# AEMBLINK-R2.net
KiCad netlist of a schematic drawn in EAGLE
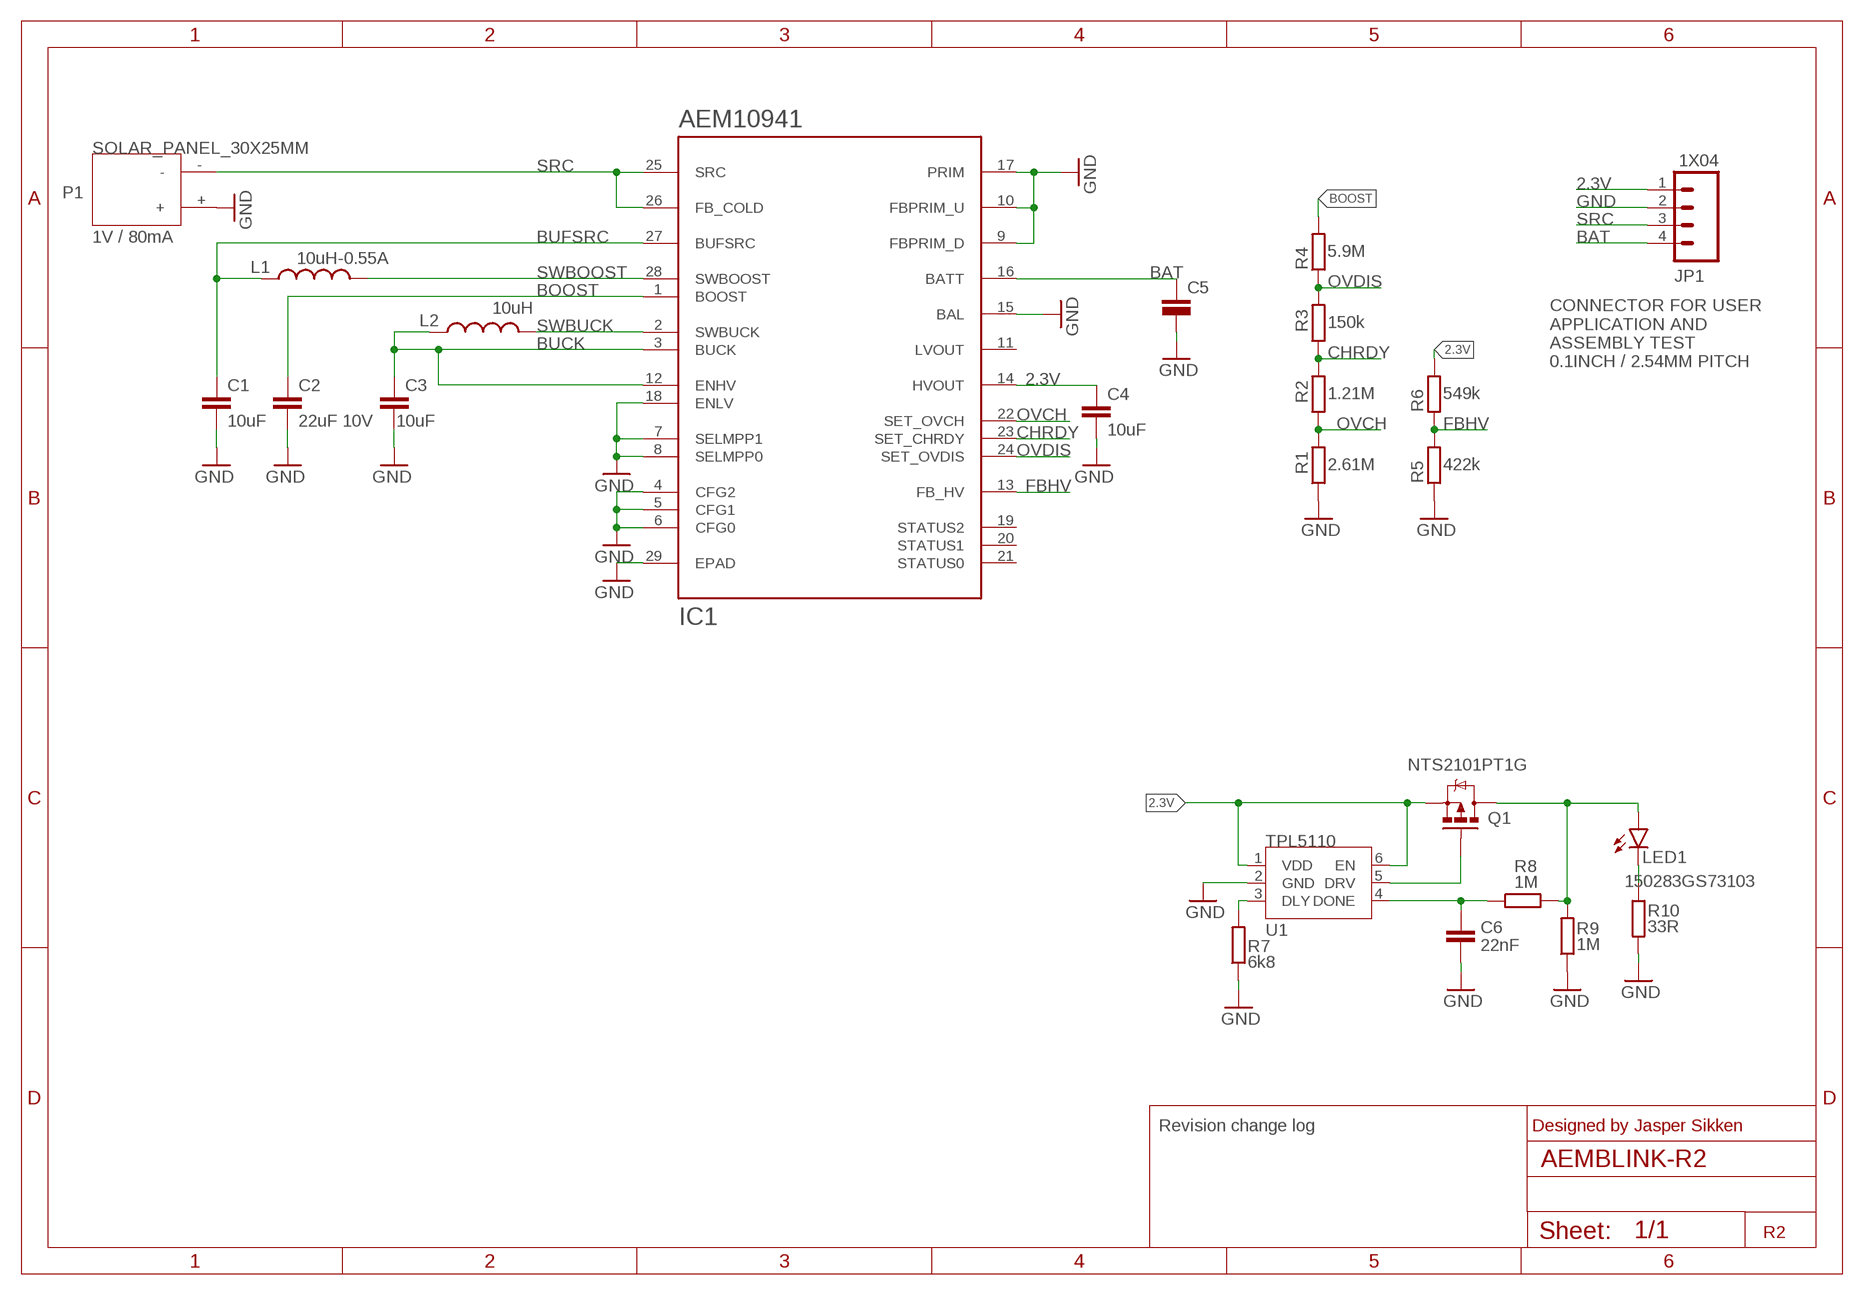
[diagram p0: schematic, sheet 1]

(export (version "E")
  (design (tool "Eeschema 10.0.6"))
  (components
    (comp (ref "C1")
      (value "10uF")
      (footprint "eagle-import:C0603")
      (fields
        (field (name "MF") "Taiyo Yuden")
        (field (name "MPN") "LMK107BBJ106MALT")
        (field (name "MF_1") "KEYSTONE")
        (field (name "MPN_1") "1049P")
      )
      (libsource (lib "eagle-import") (part "C0603_10UF"))
    )
    (comp (ref "C2")
      (value "22uF 10V")
      (footprint "eagle-import:C0603")
      (fields
        (field (name "MF") "Murata")
        (field (name "MPN") "GRM188R61A226ME15D")
        (field (name "MF_1") "TDK")
        (field (name "MPN_1") "CGA5L1X7S1A226M160AC")
      )
      (libsource (lib "eagle-import") (part "C0603_22UF"))
    )
    (comp (ref "C3")
      (value "10uF")
      (footprint "eagle-import:C0603")
      (fields
        (field (name "MF") "Taiyo Yuden")
        (field (name "MPN") "LMK107BBJ106MALT")
        (field (name "MF_1") "KEYSTONE")
        (field (name "MPN_1") "1049P")
      )
      (libsource (lib "eagle-import") (part "C0603_10UF"))
    )
    (comp (ref "C4")
      (value "10uF")
      (footprint "eagle-import:C0603")
      (fields
        (field (name "MF") "Taiyo Yuden")
        (field (name "MPN") "LMK107BBJ106MALT")
        (field (name "MF_1") "KEYSTONE")
        (field (name "MPN_1") "1049P")
      )
      (libsource (lib "eagle-import") (part "C0603_10UF"))
    )
    (comp (ref "C5")
      (value "SUPERCAPVEL08203R8306G")
      (footprint "eagle-import:C_RADIAL_20L8D5P0.8H_HOR")
      (libsource (lib "eagle-import") (part "SUPERCAPVEL08203R8306G"))
    )
    (comp (ref "C6")
      (value "22nF")
      (footprint "eagle-import:C0603")
      (libsource (lib "eagle-import") (part "C0603_10NF"))
    )
    (comp (ref "IC1")
      (value "AEM10941")
      (footprint "eagle-import:QFN50P505X505X90-28")
      (fields (field (name "MF") "e-peas"))
      (libsource (lib "eagle-import") (part "AEM10941"))
    )
    (comp (ref "JP1")
      (value "1X04")
      (footprint "eagle-import:1X04_2.54MM_ROUND_NOSILK")
      (libsource (lib "eagle-import") (part "1X04"))
    )
    (comp (ref "L1")
      (value "10uH-0.55A")
      (footprint "eagle-import:LPS4012")
      (fields
        (field (name "MF") "Coilcraft")
        (field (name "MPN") "LPS4012-103MRB")
        (field (name "MF_1") "BOURNS")
        (field (name "MPN_1") "SRN2009T-100M")
      )
      (libsource (lib "eagle-import") (part "L3.9X3.9_10UH_0.55A"))
    )
    (comp (ref "L2")
      (value "10uH")
      (footprint "eagle-import:L0603")
      (fields
        (field (name "MF") "TDK")
        (field (name "MPN") "MLZ1608M100WT")
        (field (name "MF_1") "TAIYO YUDEN")
        (field (name "MPN_1") "CK2125100M-T")
      )
      (libsource (lib "eagle-import") (part "L0603_10UH"))
    )
    (comp (ref "LED1")
      (value "150283GS73103")
      (footprint "eagle-import:150283GS73103")
      (libsource (lib "eagle-import") (part "150283GS73103"))
    )
    (comp (ref "P1")
      (value "SOLAR_PANEL_30X25MM")
      (footprint "eagle-import:SOLAR_PANEL_30X25")
      (libsource (lib "eagle-import") (part "SOLAR_PANEL_30X25MM"))
    )
    (comp (ref "Q1")
      (value "NTS2101PT1G")
      (footprint "eagle-import:SOT323")
      (libsource (lib "eagle-import") (part "MOSFET-P-CHANNEL-DMP2160UW"))
    )
    (comp (ref "R1")
      (value "2.61M")
      (footprint "eagle-import:R0402")
      (fields (field (name "MF") "Walsin") (field (name "MPN") "WR04X1004FTL"))
      (libsource (lib "eagle-import") (part "R0402_1M"))
    )
    (comp (ref "R2")
      (value "1.21M")
      (footprint "eagle-import:R0402")
      (fields (field (name "MF") "Walsin") (field (name "MPN") "WR04X1004FTL"))
      (libsource (lib "eagle-import") (part "R0402_1M"))
    )
    (comp (ref "R3")
      (value "150k")
      (footprint "eagle-import:R0402")
      (fields (field (name "MF") "Walsin") (field (name "MPN") "WR04X1004FTL"))
      (libsource (lib "eagle-import") (part "R0402_1M"))
    )
    (comp (ref "R4")
      (value "5.9M")
      (footprint "eagle-import:R0402")
      (fields (field (name "MF") "Walsin") (field (name "MPN") "WR04X1004FTL"))
      (libsource (lib "eagle-import") (part "R0402_1M"))
    )
    (comp (ref "R5")
      (value "422k")
      (footprint "eagle-import:R0402")
      (fields (field (name "MF") "Walsin") (field (name "MPN") "WR04X1004FTL"))
      (libsource (lib "eagle-import") (part "R0402_1M"))
    )
    (comp (ref "R6")
      (value "549k")
      (footprint "eagle-import:R0402")
      (fields (field (name "MF") "Walsin") (field (name "MPN") "WR04X1004FTL"))
      (libsource (lib "eagle-import") (part "R0402_1M"))
    )
    (comp (ref "R7")
      (value "6k8")
      (footprint "eagle-import:R0603")
      (libsource (lib "eagle-import") (part "R-EU_R0603"))
    )
    (comp (ref "R8")
      (value "1M")
      (footprint "eagle-import:R0603")
      (libsource (lib "eagle-import") (part "R0603_1M"))
    )
    (comp (ref "R9")
      (value "1M")
      (footprint "eagle-import:R0603")
      (libsource (lib "eagle-import") (part "R0603_1M"))
    )
    (comp (ref "R10")
      (value "33R")
      (footprint "eagle-import:R0603")
      (libsource (lib "eagle-import") (part "R-EU_R0603"))
    )
    (comp (ref "U1")
      (value "TPL5110")
      (footprint "eagle-import:SOT23-6")
      (libsource (lib "eagle-import") (part "TPL5110"))
    )
  )
  (nets
    (net (code "1") (name "/BAT") (class "Default")
      (node (ref "C5") (pin "+") (pinfunction "+_+") (pintype "passive"))
      (node (ref "IC1") (pin "16") (pinfunction "BATT_16") (pintype "bidirectional"))
      (node (ref "JP1") (pin "4") (pinfunction "4_4") (pintype "passive"))
    )
    (net (code "2") (name "/BUCK") (class "Default")
      (node (ref "C3") (pin "1") (pinfunction "1_1") (pintype "passive"))
      (node (ref "IC1") (pin "12") (pinfunction "ENHV_12") (pintype "bidirectional"))
      (node (ref "IC1") (pin "3") (pinfunction "BUCK_3") (pintype "bidirectional"))
      (node (ref "L2") (pin "1") (pinfunction "1_1") (pintype "passive"))
    )
    (net (code "3") (name "/BUFSRC") (class "Default")
      (node (ref "C1") (pin "1") (pinfunction "1_1") (pintype "passive"))
      (node (ref "IC1") (pin "27") (pinfunction "BUFSRC_27") (pintype "power_in"))
      (node (ref "L1") (pin "1") (pinfunction "1_1") (pintype "passive"))
    )
    (net (code "4") (name "/CHRDY") (class "Default")
      (node (ref "IC1") (pin "23") (pinfunction "SET_CHRDY_23") (pintype "bidirectional"))
      (node (ref "R2") (pin "2") (pinfunction "2_2") (pintype "passive"))
      (node (ref "R3") (pin "1") (pinfunction "1_1") (pintype "passive"))
    )
    (net (code "5") (name "/FBHV") (class "Default")
      (node (ref "IC1") (pin "13") (pinfunction "FB_HV_13") (pintype "bidirectional"))
      (node (ref "R5") (pin "2") (pinfunction "2_2") (pintype "passive"))
      (node (ref "R6") (pin "1") (pinfunction "1_1") (pintype "passive"))
    )
    (net (code "6") (name "/OVCH") (class "Default")
      (node (ref "IC1") (pin "22") (pinfunction "SET_OVCH_22") (pintype "bidirectional"))
      (node (ref "R1") (pin "2") (pinfunction "2_2") (pintype "passive"))
      (node (ref "R2") (pin "1") (pinfunction "1_1") (pintype "passive"))
    )
    (net (code "7") (name "/OVDIS") (class "Default")
      (node (ref "IC1") (pin "24") (pinfunction "SET_OVDIS_24") (pintype "bidirectional"))
      (node (ref "R3") (pin "2") (pinfunction "2_2") (pintype "passive"))
      (node (ref "R4") (pin "1") (pinfunction "1_1") (pintype "passive"))
    )
    (net (code "8") (name "/SRC") (class "Default")
      (node (ref "IC1") (pin "25") (pinfunction "SRC_25") (pintype "power_in"))
      (node (ref "IC1") (pin "26") (pinfunction "FB_COLD_26") (pintype "input"))
      (node (ref "JP1") (pin "3") (pinfunction "3_3") (pintype "passive"))
      (node (ref "P1") (pin "-") (pinfunction "-_-") (pintype "bidirectional"))
    )
    (net (code "9") (name "/SWBOOST") (class "Default")
      (node (ref "IC1") (pin "28") (pinfunction "SWBOOST_28") (pintype "power_in"))
      (node (ref "L1") (pin "2") (pinfunction "2_2") (pintype "passive"))
    )
    (net (code "10") (name "/SWBUCK") (class "Default")
      (node (ref "IC1") (pin "2") (pinfunction "SWBUCK_2") (pintype "bidirectional"))
      (node (ref "L2") (pin "2") (pinfunction "2_2") (pintype "passive"))
    )
    (net (code "11") (name "2.3V") (class "Default")
      (node (ref "C4") (pin "1") (pinfunction "1_1") (pintype "passive"))
      (node (ref "IC1") (pin "14") (pinfunction "HVOUT_14") (pintype "bidirectional"))
      (node (ref "JP1") (pin "1") (pinfunction "1_1") (pintype "passive"))
      (node (ref "Q1") (pin "2") (pinfunction "S_2") (pintype "passive"))
      (node (ref "R6") (pin "2") (pinfunction "2_2") (pintype "passive"))
      (node (ref "U1") (pin "1") (pinfunction "VDD_1") (pintype "bidirectional"))
      (node (ref "U1") (pin "6") (pinfunction "EN_6") (pintype "bidirectional"))
    )
    (net (code "12") (name "BOOST") (class "Default")
      (node (ref "C2") (pin "1") (pinfunction "1_1") (pintype "passive"))
      (node (ref "IC1") (pin "1") (pinfunction "BOOST_1") (pintype "bidirectional"))
      (node (ref "R4") (pin "2") (pinfunction "2_2") (pintype "passive"))
    )
    (net (code "13") (name "GND") (class "Default")
      (node (ref "C1") (pin "2") (pinfunction "2_2") (pintype "passive"))
      (node (ref "C2") (pin "2") (pinfunction "2_2") (pintype "passive"))
      (node (ref "C3") (pin "2") (pinfunction "2_2") (pintype "passive"))
      (node (ref "C4") (pin "2") (pinfunction "2_2") (pintype "passive"))
      (node (ref "C5") (pin "-") (pinfunction "-_-") (pintype "passive"))
      (node (ref "C6") (pin "2") (pinfunction "2_2") (pintype "passive"))
      (node (ref "IC1") (pin "10") (pinfunction "FBPRIM_U_10") (pintype "bidirectional"))
      (node (ref "IC1") (pin "15") (pinfunction "BAL_15") (pintype "bidirectional"))
      (node (ref "IC1") (pin "17") (pinfunction "PRIM_17") (pintype "bidirectional"))
      (node (ref "IC1") (pin "18") (pinfunction "ENLV_18") (pintype "bidirectional"))
      (node (ref "IC1") (pin "29") (pinfunction "EPAD_29") (pintype "power_in"))
      (node (ref "IC1") (pin "4") (pinfunction "CFG2_4") (pintype "bidirectional"))
      (node (ref "IC1") (pin "5") (pinfunction "CFG1_5") (pintype "bidirectional"))
      (node (ref "IC1") (pin "6") (pinfunction "CFG0_6") (pintype "bidirectional"))
      (node (ref "IC1") (pin "7") (pinfunction "SELMPP1_7") (pintype "bidirectional"))
      (node (ref "IC1") (pin "8") (pinfunction "SELMPP0_8") (pintype "bidirectional"))
      (node (ref "IC1") (pin "9") (pinfunction "FBPRIM_D_9") (pintype "bidirectional"))
      (node (ref "JP1") (pin "2") (pinfunction "2_2") (pintype "passive"))
      (node (ref "P1") (pin "+") (pinfunction "+_+") (pintype "bidirectional"))
      (node (ref "R1") (pin "1") (pinfunction "1_1") (pintype "passive"))
      (node (ref "R10") (pin "2") (pinfunction "2_2") (pintype "passive"))
      (node (ref "R5") (pin "1") (pinfunction "1_1") (pintype "passive"))
      (node (ref "R7") (pin "1") (pinfunction "1_1") (pintype "passive"))
      (node (ref "R9") (pin "1") (pinfunction "1_1") (pintype "passive"))
      (node (ref "U1") (pin "2") (pinfunction "GND_2") (pintype "bidirectional"))
    )
    (net (code "14") (name "Net-(LED1-A)") (class "Default")
      (node (ref "LED1") (pin "1") (pinfunction "A_1") (pintype "passive"))
      (node (ref "Q1") (pin "3") (pinfunction "D_3") (pintype "passive"))
      (node (ref "R8") (pin "2") (pinfunction "2_2") (pintype "passive"))
      (node (ref "R9") (pin "2") (pinfunction "2_2") (pintype "passive"))
    )
    (net (code "15") (name "Net-(LED1-C)") (class "Default")
      (node (ref "LED1") (pin "2") (pinfunction "C_2") (pintype "passive"))
      (node (ref "R10") (pin "1") (pinfunction "1_1") (pintype "passive"))
    )
    (net (code "16") (name "Net-(Q1-G)") (class "Default")
      (node (ref "Q1") (pin "1") (pinfunction "G_1") (pintype "passive"))
      (node (ref "U1") (pin "5") (pinfunction "DRV_5") (pintype "bidirectional"))
    )
    (net (code "17") (name "Net-(U1-DLY)") (class "Default")
      (node (ref "R7") (pin "2") (pinfunction "2_2") (pintype "passive"))
      (node (ref "U1") (pin "3") (pinfunction "DLY_3") (pintype "bidirectional"))
    )
    (net (code "18") (name "Net-(U1-DONE)") (class "Default")
      (node (ref "C6") (pin "1") (pinfunction "1_1") (pintype "passive"))
      (node (ref "R8") (pin "1") (pinfunction "1_1") (pintype "passive"))
      (node (ref "U1") (pin "4") (pinfunction "DONE_4") (pintype "bidirectional"))
    )
    (net (code "19") (name "unconnected-(IC1-LVOUT-Pad11)") (class "Default")
      (node (ref "IC1") (pin "11") (pinfunction "LVOUT_11") (pintype "bidirectional"))
    )
    (net (code "20") (name "unconnected-(IC1-STATUS0-Pad21)") (class "Default")
      (node (ref "IC1") (pin "21") (pinfunction "STATUS0_21") (pintype "bidirectional"))
    )
    (net (code "21") (name "unconnected-(IC1-STATUS1-Pad20)") (class "Default")
      (node (ref "IC1") (pin "20") (pinfunction "STATUS1_20") (pintype "bidirectional"))
    )
    (net (code "22") (name "unconnected-(IC1-STATUS2-Pad19)") (class "Default")
      (node (ref "IC1") (pin "19") (pinfunction "STATUS2_19") (pintype "bidirectional"))
    )
  )
)
